# BlockDiagram.net
KiCad netlist of a schematic drawn in EAGLE
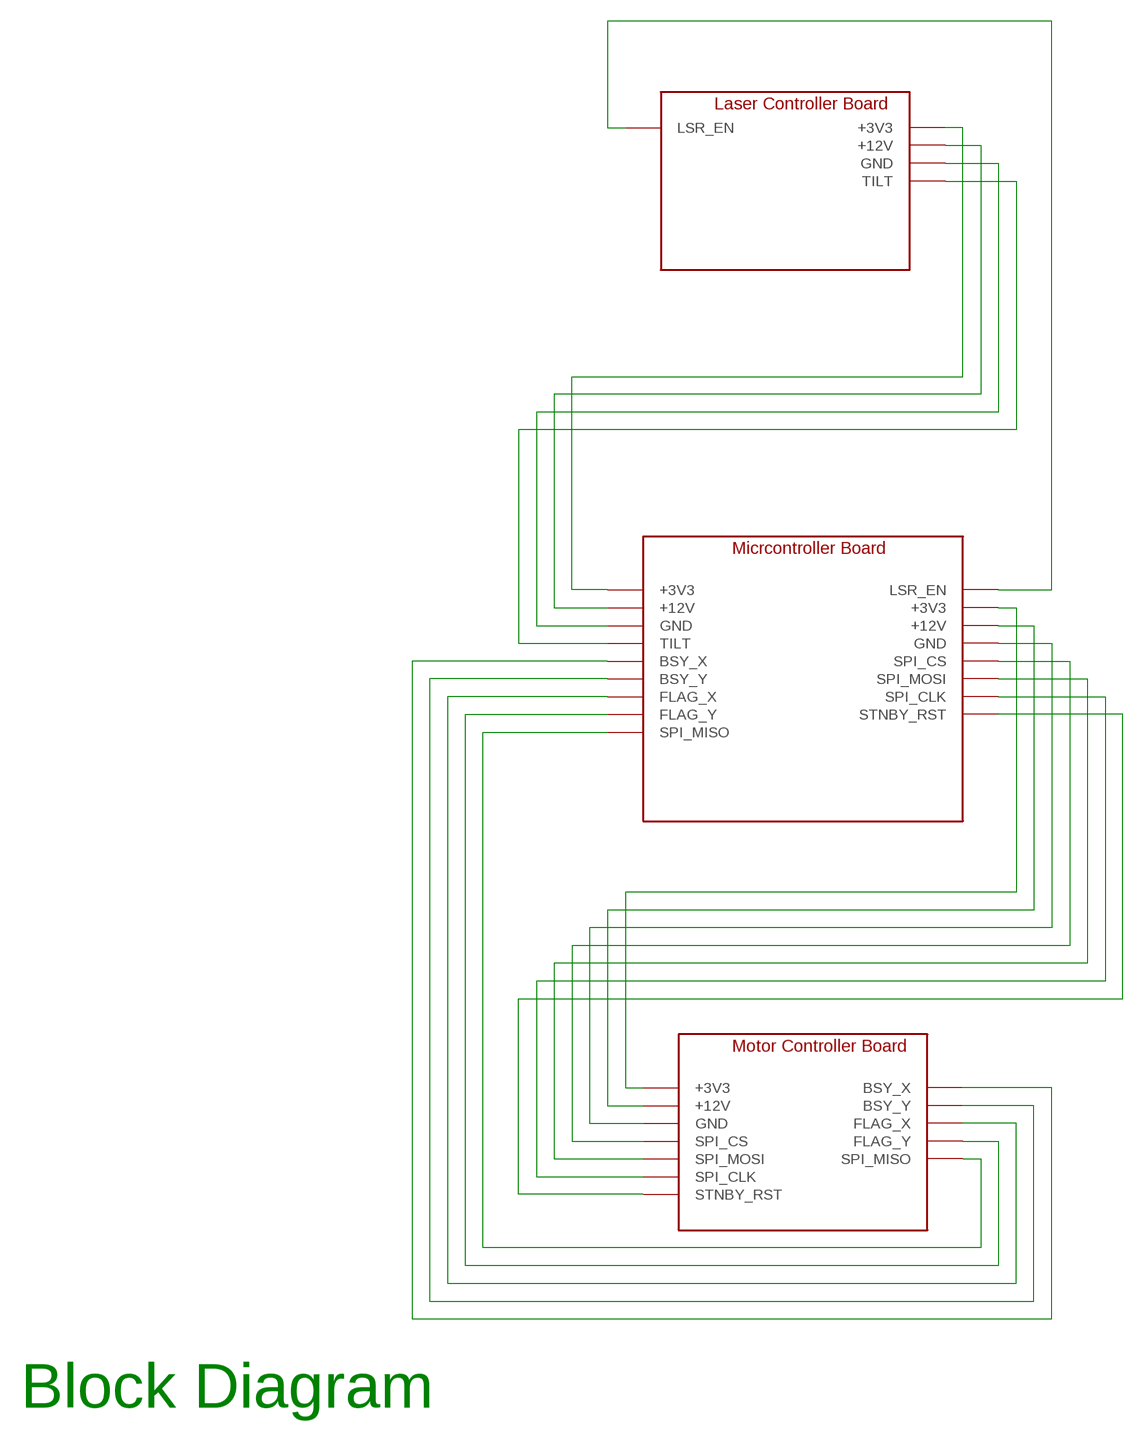
[diagram p0: schematic, sheet 1]

(export (version "E")
  (design (tool "Eeschema 10.0.6"))
  (components
    (comp (ref "U$1")
      (value "MICROCONTROLLER_BOARD")
      (footprint "eagle-import:MICROCONTROLLER_BOARD")
      (libsource (lib "eagle-import") (part "MICROCONTROLLER_BOARD"))
    )
    (comp (ref "U$2")
      (value "LASER_CONTROLLER_BOARD")
      (footprint "eagle-import:LASER_CONTROLLER_BOARD")
      (libsource (lib "eagle-import") (part "LASER_CONTROLLER_BOARD"))
    )
    (comp (ref "U$3")
      (value "MOTOR_CONTROLLER_BOARD")
      (footprint "eagle-import:MOTOR_CONTROLLER_BOARD")
      (libsource (lib "eagle-import") (part "MOTOR_CONTROLLER_BOARD"))
    )
  )
  (nets
    (net (code "1") (name "Net-(U$1-BSY_X)") (class "Default")
      (node (ref "U$1") (pin "P$5") (pinfunction "BSY_X_P$5") (pintype "bidirectional"))
      (node (ref "U$3") (pin "P$3") (pinfunction "BSY_X_P$3") (pintype "bidirectional"))
    )
    (net (code "2") (name "Net-(U$1-BSY_Y)") (class "Default")
      (node (ref "U$1") (pin "P$6") (pinfunction "BSY_Y_P$6") (pintype "bidirectional"))
      (node (ref "U$3") (pin "P$4") (pinfunction "BSY_Y_P$4") (pintype "bidirectional"))
    )
    (net (code "3") (name "Net-(U$1-FLAG_X)") (class "Default")
      (node (ref "U$1") (pin "P$7") (pinfunction "FLAG_X_P$7") (pintype "bidirectional"))
      (node (ref "U$3") (pin "P$5") (pinfunction "FLAG_X_P$5") (pintype "bidirectional"))
    )
    (net (code "4") (name "Net-(U$1-FLAG_Y)") (class "Default")
      (node (ref "U$1") (pin "P$8") (pinfunction "FLAG_Y_P$8") (pintype "bidirectional"))
      (node (ref "U$3") (pin "P$6") (pinfunction "FLAG_Y_P$6") (pintype "bidirectional"))
    )
    (net (code "5") (name "Net-(U$1-LSR_EN)") (class "Default")
      (node (ref "U$1") (pin "P$11") (pinfunction "LSR_EN_P$11") (pintype "output"))
      (node (ref "U$2") (pin "P$4") (pinfunction "LSR_EN_P$4") (pintype "input"))
    )
    (net (code "6") (name "Net-(U$1-SPI_CLK)") (class "Default")
      (node (ref "U$1") (pin "P$12") (pinfunction "SPI_CLK_P$12") (pintype "bidirectional"))
      (node (ref "U$3") (pin "P$8") (pinfunction "SPI_CLK_P$8") (pintype "bidirectional"))
    )
    (net (code "7") (name "Net-(U$1-SPI_CS)") (class "Default")
      (node (ref "U$1") (pin "P$13") (pinfunction "SPI_CS_P$13") (pintype "bidirectional"))
      (node (ref "U$3") (pin "P$9") (pinfunction "SPI_CS_P$9") (pintype "bidirectional"))
    )
    (net (code "8") (name "Net-(U$1-SPI_MISO)") (class "Default")
      (node (ref "U$1") (pin "P$14") (pinfunction "SPI_MISO_P$14") (pintype "bidirectional"))
      (node (ref "U$3") (pin "P$10") (pinfunction "SPI_MISO_P$10") (pintype "bidirectional"))
    )
    (net (code "9") (name "Net-(U$1-SPI_MOSI)") (class "Default")
      (node (ref "U$1") (pin "P$15") (pinfunction "SPI_MOSI_P$15") (pintype "bidirectional"))
      (node (ref "U$3") (pin "P$11") (pinfunction "SPI_MOSI_P$11") (pintype "bidirectional"))
    )
    (net (code "10") (name "Net-(U$1-STNBY_RST)") (class "Default")
      (node (ref "U$1") (pin "P$16") (pinfunction "STNBY_RST_P$16") (pintype "bidirectional"))
      (node (ref "U$3") (pin "P$12") (pinfunction "STNBY_RST_P$12") (pintype "bidirectional"))
    )
    (net (code "11") (name "Net-(U$1-TILT)") (class "Default")
      (node (ref "U$1") (pin "P$17") (pinfunction "TILT_P$17") (pintype "input"))
      (node (ref "U$2") (pin "P$5") (pinfunction "TILT_P$5") (pintype "output"))
    )
    (net (code "12") (name "Net-(U$2-+3V3)") (class "Default")
      (node (ref "U$1") (pin "P$1") (pinfunction "+3V3_P$1") (pintype "input"))
      (node (ref "U$2") (pin "P$1") (pinfunction "+3V3_P$1") (pintype "output"))
    )
    (net (code "13") (name "Net-(U$2-+12V)") (class "Default")
      (node (ref "U$1") (pin "P$3") (pinfunction "+12V_P$3") (pintype "input"))
      (node (ref "U$2") (pin "P$2") (pinfunction "+12V_P$2") (pintype "output"))
    )
    (net (code "14") (name "Net-(U$2-GND)") (class "Default")
      (node (ref "U$1") (pin "P$9") (pinfunction "GND_P$9") (pintype "input"))
      (node (ref "U$2") (pin "P$3") (pinfunction "GND_P$3") (pintype "output"))
    )
    (net (code "15") (name "Net-(U$3-+3V3)") (class "Default")
      (node (ref "U$1") (pin "P$2") (pinfunction "+3V3_P$2") (pintype "bidirectional"))
      (node (ref "U$3") (pin "P$1") (pinfunction "+3V3_P$1") (pintype "bidirectional"))
    )
    (net (code "16") (name "Net-(U$3-+12V)") (class "Default")
      (node (ref "U$1") (pin "P$4") (pinfunction "+12V_P$4") (pintype "output"))
      (node (ref "U$3") (pin "P$2") (pinfunction "+12V_P$2") (pintype "bidirectional"))
    )
    (net (code "17") (name "Net-(U$3-GND)") (class "Default")
      (node (ref "U$1") (pin "P$10") (pinfunction "GND_P$10") (pintype "input"))
      (node (ref "U$3") (pin "P$7") (pinfunction "GND_P$7") (pintype "bidirectional"))
    )
  )
)
